# CPU_ETH.net
KiCad netlist of a schematic drawn in Altium Designer
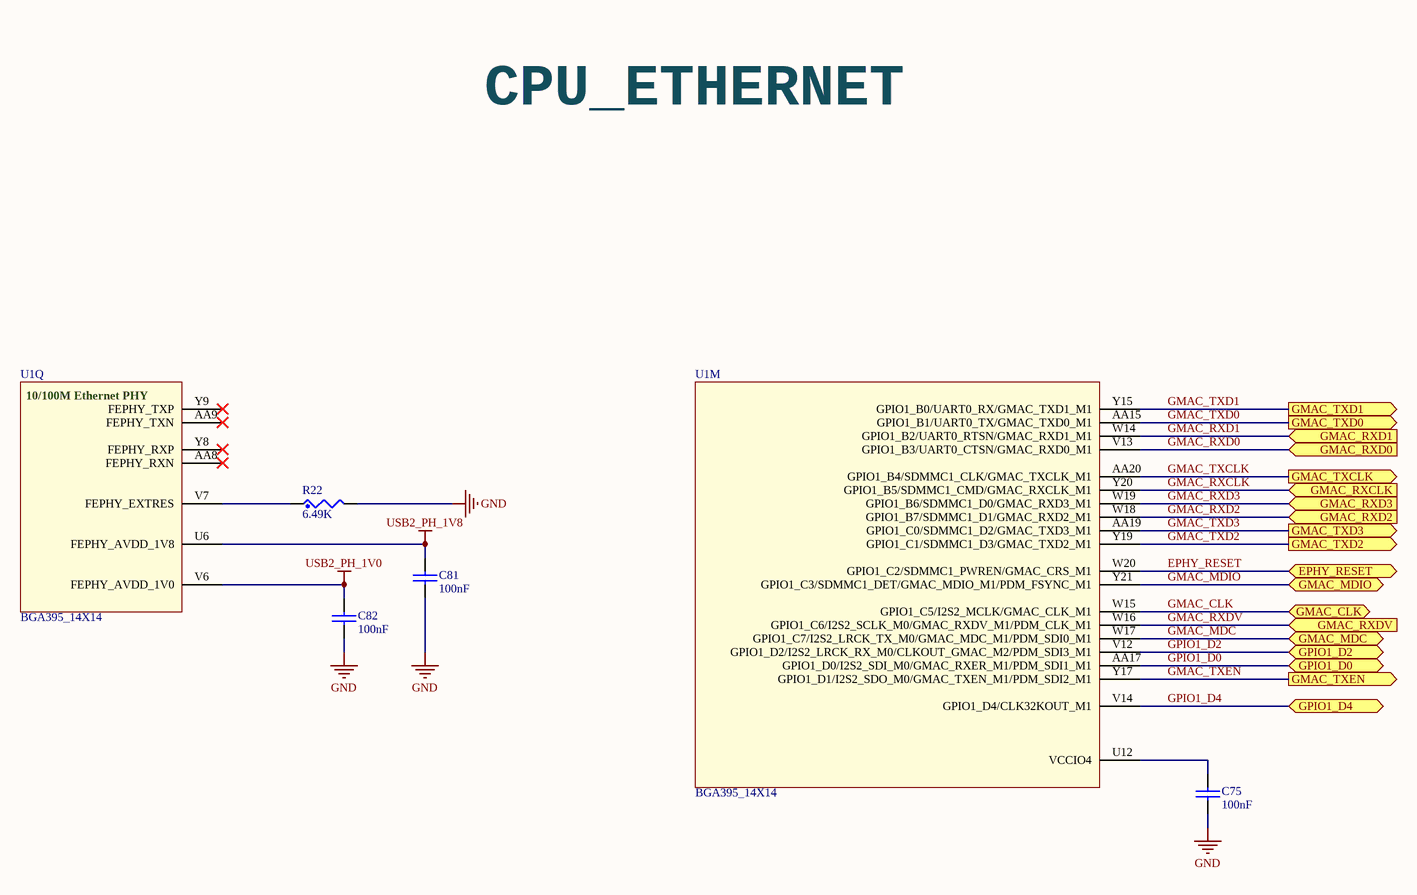
[diagram p0: CPU_ETH.SchDoc]

(export (version "E")
  (design (tool "Eeschema 10.0.6"))
  (components
    (comp (ref "C75")
      (value "100nF")
      (footprint "0402_CC - C")
      (libsource (lib "AAR_RockChip_RK3328") (part "CAP_NP"))
    )
    (comp (ref "C81")
      (value "100nF")
      (footprint "0402_CC - C")
      (libsource (lib "AAR_RockChip_RK3328") (part "CAP_NP"))
    )
    (comp (ref "C82")
      (value "100nF")
      (footprint "0402_CC - C")
      (libsource (lib "AAR_RockChip_RK3328") (part "CAP_NP"))
    )
    (comp (ref "R22")
      (value "6.49K")
      (footprint "0402_CR")
      (libsource (lib "AAR_RockChip_RK3328") (part "RES"))
    )
    (comp (ref "U1")
      (value "BGA395_14X14")
      (footprint "BGA395C65P21X21_1750X1750X117")
      (description "By AAR")
      (libsource (lib "AAR_RockChip_RK3328") (part "RK3328"))
    )
  )
  (nets
    (net (code "1") (name "/EPHY_RESET") (class "Default")
      (node (ref "U1") (pin "W20") (pinfunction "GPIO1_C2/SDMMC1_PWREN/GMAC_CRS_M1_W20") (pintype "passive"))
    )
    (net (code "2") (name "/GMAC_CLK") (class "Default")
      (node (ref "U1") (pin "W15") (pinfunction "GPIO1_C5/I2S2_MCLK/GMAC_CLK_M1_W15") (pintype "passive"))
    )
    (net (code "3") (name "/GMAC_MDC") (class "Default")
      (node (ref "U1") (pin "W17") (pinfunction "GPIO1_C7/I2S2_LRCK_TX_M0/GMAC_MDC_M1/PDM_SDI0_M1_W17") (pintype "passive"))
    )
    (net (code "4") (name "/GMAC_MDIO") (class "Default")
      (node (ref "U1") (pin "Y21") (pinfunction "GPIO1_C3/SDMMC1_DET/GMAC_MDIO_M1/PDM_FSYNC_M1_Y21") (pintype "passive"))
    )
    (net (code "5") (name "/GMAC_RXCLK") (class "Default")
      (node (ref "U1") (pin "Y20") (pinfunction "GPIO1_B5/SDMMC1_CMD/GMAC_RXCLK_M1_Y20") (pintype "passive"))
    )
    (net (code "6") (name "/GMAC_RXD0") (class "Default")
      (node (ref "U1") (pin "V13") (pinfunction "GPIO1_B3/UART0_CTSN/GMAC_RXD0_M1_V13") (pintype "passive"))
    )
    (net (code "7") (name "/GMAC_RXD1") (class "Default")
      (node (ref "U1") (pin "W14") (pinfunction "GPIO1_B2/UART0_RTSN/GMAC_RXD1_M1_W14") (pintype "passive"))
    )
    (net (code "8") (name "/GMAC_RXD2") (class "Default")
      (node (ref "U1") (pin "W18") (pinfunction "GPIO1_B7/SDMMC1_D1/GMAC_RXD2_M1_W18") (pintype "passive"))
    )
    (net (code "9") (name "/GMAC_RXD3") (class "Default")
      (node (ref "U1") (pin "W19") (pinfunction "GPIO1_B6/SDMMC1_D0/GMAC_RXD3_M1_W19") (pintype "passive"))
    )
    (net (code "10") (name "/GMAC_RXDV") (class "Default")
      (node (ref "U1") (pin "W16") (pinfunction "GPIO1_C6/I2S2_SCLK_M0/GMAC_RXDV_M1/PDM_CLK_M1_W16") (pintype "passive"))
    )
    (net (code "11") (name "/GMAC_TXCLK") (class "Default")
      (node (ref "U1") (pin "AA20") (pinfunction "GPIO1_B4/SDMMC1_CLK/GMAC_TXCLK_M1_AA20") (pintype "passive"))
    )
    (net (code "12") (name "/GMAC_TXD0") (class "Default")
      (node (ref "U1") (pin "AA15") (pinfunction "GPIO1_B1/UART0_TX/GMAC_TXD0_M1_AA15") (pintype "passive"))
    )
    (net (code "13") (name "/GMAC_TXD1") (class "Default")
      (node (ref "U1") (pin "Y15") (pinfunction "GPIO1_B0/UART0_RX/GMAC_TXD1_M1_Y15") (pintype "passive"))
    )
    (net (code "14") (name "/GMAC_TXD2") (class "Default")
      (node (ref "U1") (pin "Y19") (pinfunction "GPIO1_C1/SDMMC1_D3/GMAC_TXD2_M1_Y19") (pintype "passive"))
    )
    (net (code "15") (name "/GMAC_TXD3") (class "Default")
      (node (ref "U1") (pin "AA19") (pinfunction "GPIO1_C0/SDMMC1_D2/GMAC_TXD3_M1_AA19") (pintype "passive"))
    )
    (net (code "16") (name "/GMAC_TXEN") (class "Default")
      (node (ref "U1") (pin "Y17") (pinfunction "GPIO1_D1/I2S2_SDO_M0/GMAC_TXEN_M1/PDM_SDI2_M1_Y17") (pintype "passive"))
    )
    (net (code "17") (name "/GPIO1_D0") (class "Default")
      (node (ref "U1") (pin "AA17") (pinfunction "GPIO1_D0/I2S2_SDI_M0/GMAC_RXER_M1/PDM_SDI1_M1_AA17") (pintype "passive"))
    )
    (net (code "18") (name "/GPIO1_D2") (class "Default")
      (node (ref "U1") (pin "V12") (pinfunction "GPIO1_D2/I2S2_LRCK_RX_M0/CLKOUT_GMAC_M2/PDM_SDI3_M1_V12") (pintype "passive"))
    )
    (net (code "19") (name "/GPIO1_D4") (class "Default")
      (node (ref "U1") (pin "V14") (pinfunction "GPIO1_D4/CLK32KOUT_M1_V14") (pintype "passive"))
    )
    (net (code "20") (name "GND") (class "Default")
      (node (ref "C75") (pin "1") (pinfunction "1_1") (pintype "passive"))
      (node (ref "C81") (pin "2") (pinfunction "2_2") (pintype "passive"))
      (node (ref "C82") (pin "2") (pinfunction "2_2") (pintype "passive"))
      (node (ref "R22") (pin "2") (pinfunction "2_2") (pintype "passive"))
    )
    (net (code "21") (name "Net-(U1M-VCCIO4)") (class "Default")
      (node (ref "C75") (pin "2") (pinfunction "2_2") (pintype "passive"))
      (node (ref "U1") (pin "U12") (pinfunction "VCCIO4_U12") (pintype "passive"))
    )
    (net (code "22") (name "Net-(U1Q-FEPHY_EXTRES)") (class "Default")
      (node (ref "R22") (pin "1") (pinfunction "1_1") (pintype "passive"))
      (node (ref "U1") (pin "V7") (pinfunction "FEPHY_EXTRES_V7") (pintype "passive"))
    )
    (net (code "23") (name "USB2_PH_1V0") (class "Default")
      (node (ref "C82") (pin "1") (pinfunction "1_1") (pintype "passive"))
      (node (ref "U1") (pin "V6") (pinfunction "FEPHY_AVDD_1V0_V6") (pintype "passive"))
    )
    (net (code "24") (name "USB2_PH_1V8") (class "Default")
      (node (ref "C81") (pin "1") (pinfunction "1_1") (pintype "passive"))
      (node (ref "U1") (pin "U6") (pinfunction "FEPHY_AVDD_1V8_U6") (pintype "passive"))
    )
    (net (code "25") (name "unconnected-(U1Q-FEPHY_RXN-PadAA8)") (class "Default")
      (node (ref "U1") (pin "AA8") (pinfunction "FEPHY_RXN_AA8") (pintype "passive+no_connect"))
    )
    (net (code "26") (name "unconnected-(U1Q-FEPHY_RXP-PadY8)") (class "Default")
      (node (ref "U1") (pin "Y8") (pinfunction "FEPHY_RXP_Y8") (pintype "passive+no_connect"))
    )
    (net (code "27") (name "unconnected-(U1Q-FEPHY_TXN-PadAA9)") (class "Default")
      (node (ref "U1") (pin "AA9") (pinfunction "FEPHY_TXN_AA9") (pintype "passive+no_connect"))
    )
    (net (code "28") (name "unconnected-(U1Q-FEPHY_TXP-PadY9)") (class "Default")
      (node (ref "U1") (pin "Y9") (pinfunction "FEPHY_TXP_Y9") (pintype "passive+no_connect"))
    )
  )
)
